# Board1.net
KiCad netlist of a schematic drawn in EasyEDA Pro
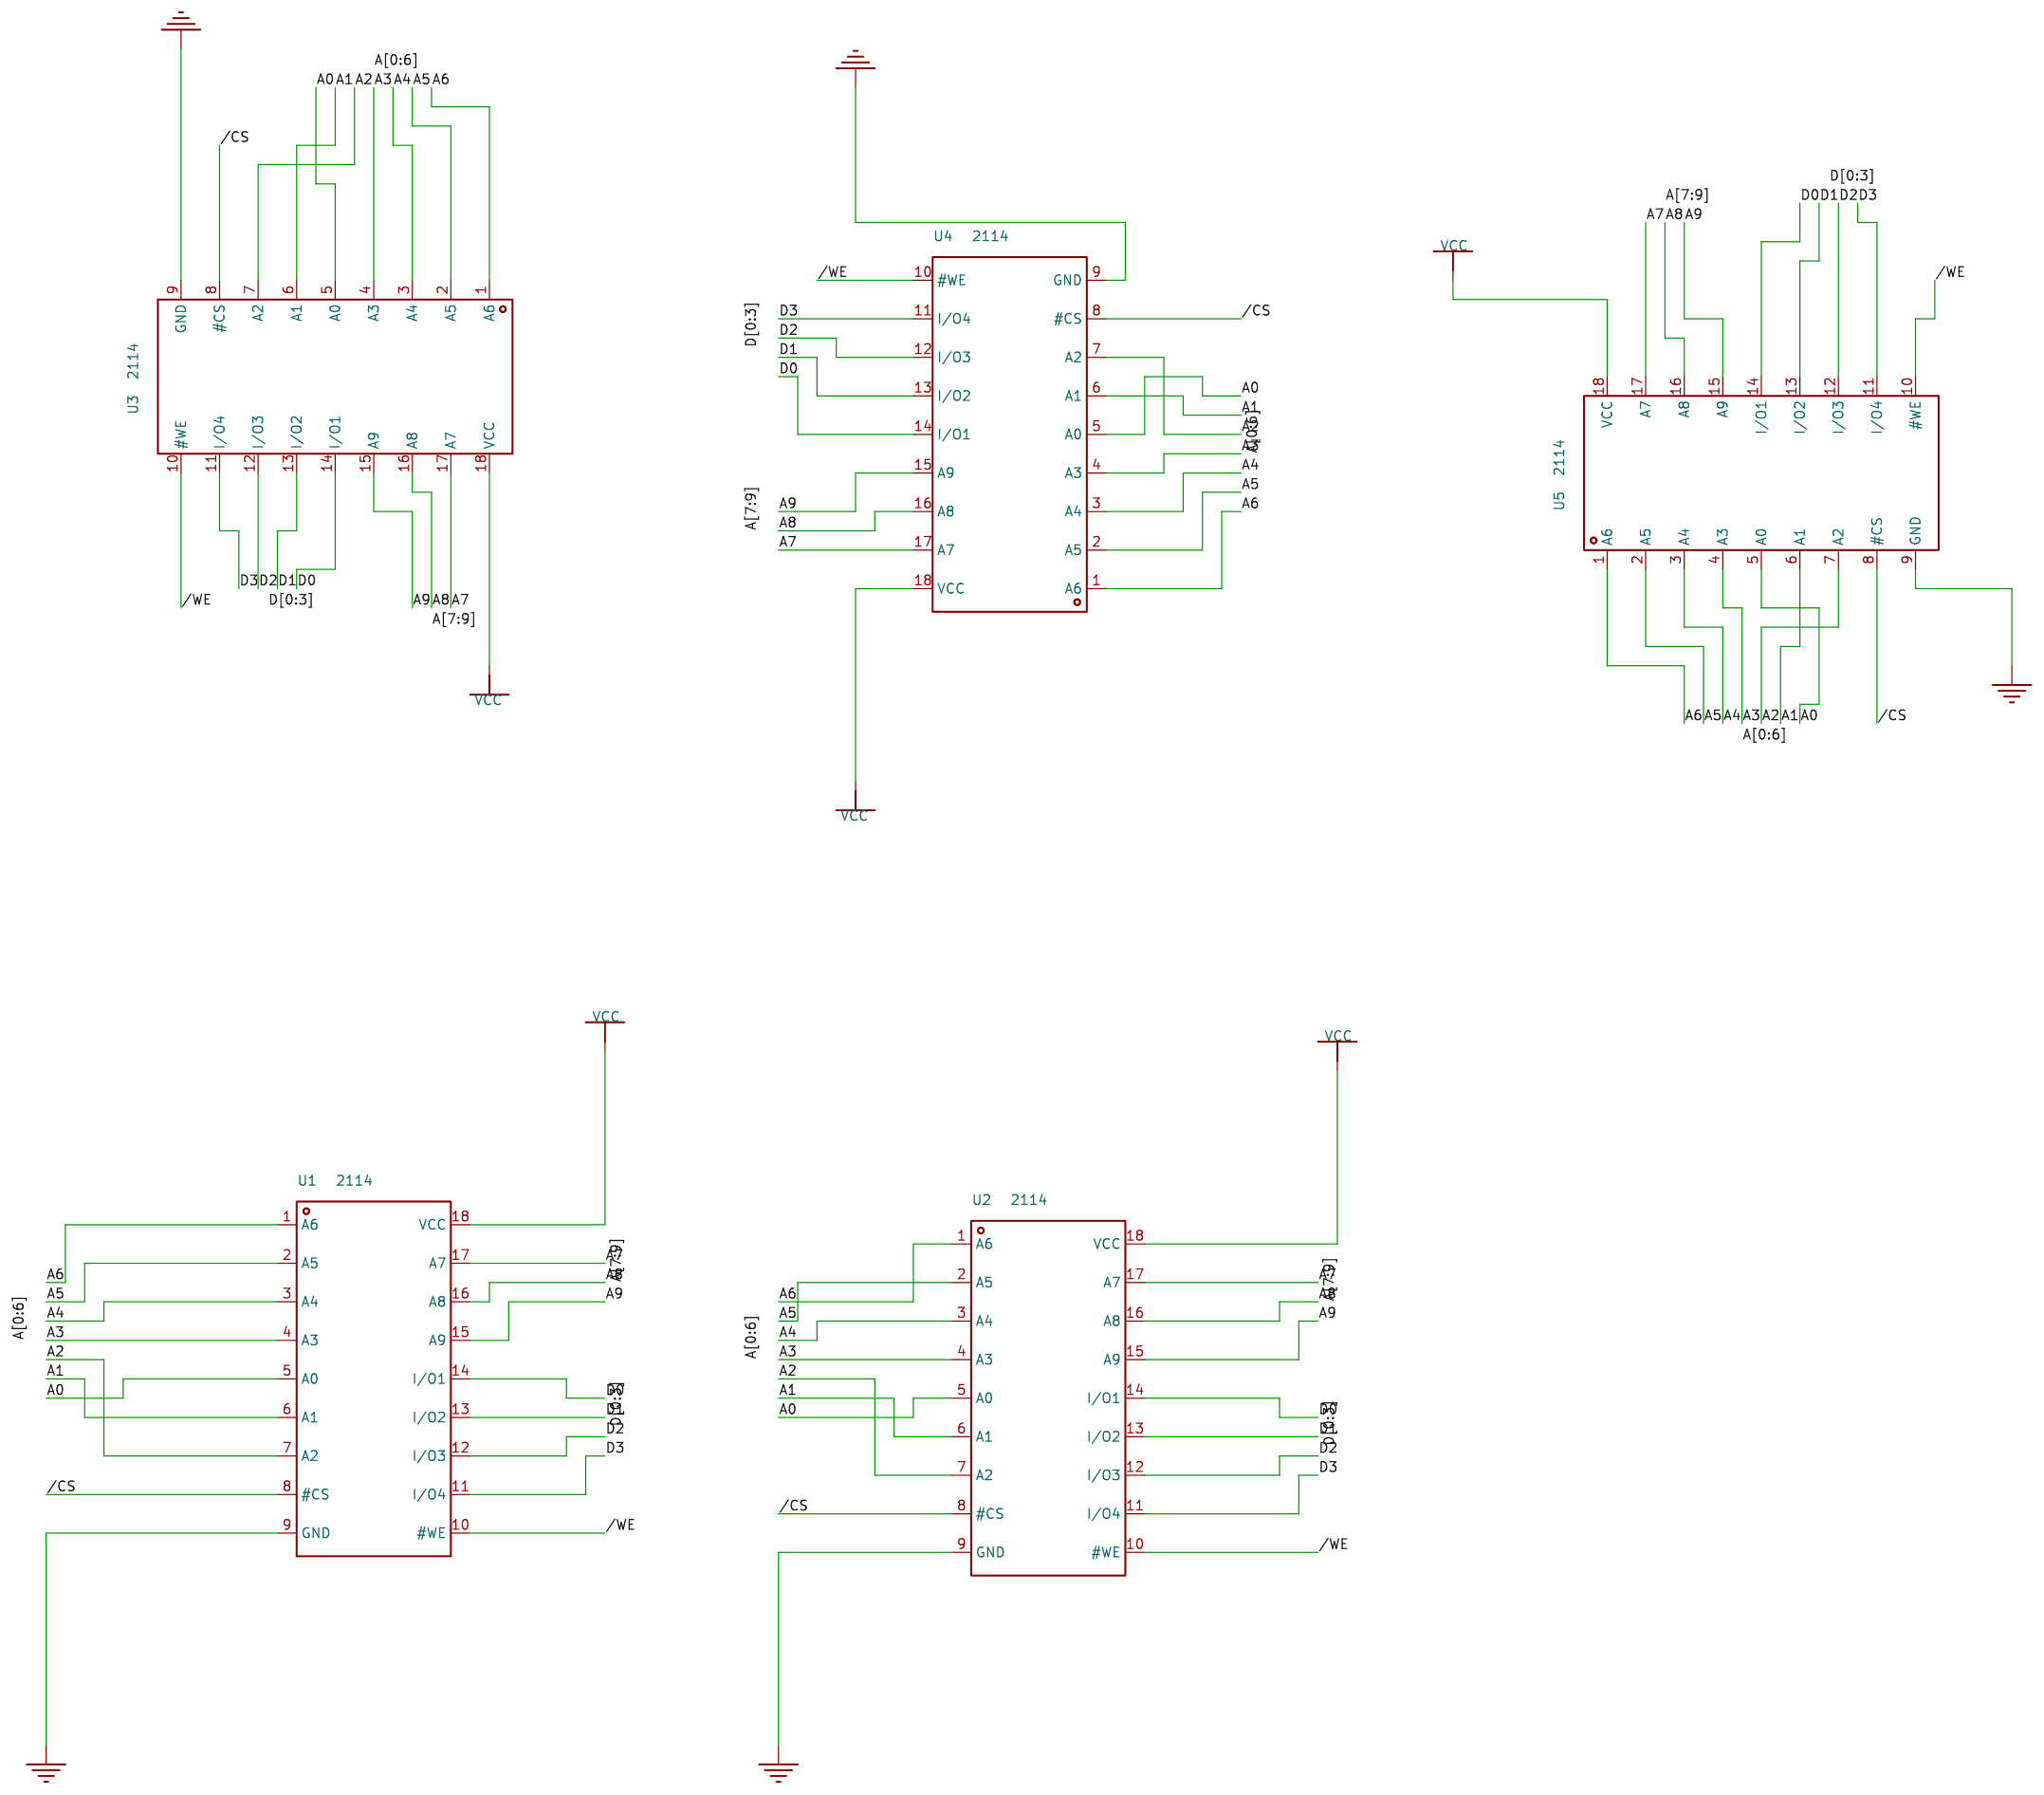
[diagram p0: schematic sheet]

(export (version "E")
  (design (tool "Eeschema 10.0.6"))
  (components
    (comp (ref "U1")
      (value "2114")
      (footprint "easyedapro:DIP-18_L23.0-W6.5-P2.54-LS7.6-BL")
      (fields (field (name "Manufacturer") "UTC"))
      (libsource (lib "easyedapro") (part "2114"))
    )
    (comp (ref "U2")
      (value "2114")
      (footprint "easyedapro:DIP-18_L23.0-W6.5-P2.54-LS7.6-BL")
      (fields (field (name "Manufacturer") "UTC"))
      (libsource (lib "easyedapro") (part "2114"))
    )
    (comp (ref "U3")
      (value "2114")
      (footprint "easyedapro:DIP-18_L23.0-W6.5-P2.54-LS7.6-BL")
      (fields (field (name "Manufacturer") "UTC"))
      (libsource (lib "easyedapro") (part "2114"))
    )
    (comp (ref "U4")
      (value "2114")
      (footprint "easyedapro:DIP-18_L23.0-W6.5-P2.54-LS7.6-BL")
      (fields (field (name "Manufacturer") "UTC"))
      (libsource (lib "easyedapro") (part "2114"))
    )
    (comp (ref "U5")
      (value "2114")
      (footprint "easyedapro:DIP-18_L23.0-W6.5-P2.54-LS7.6-BL")
      (fields (field (name "Manufacturer") "UTC"))
      (libsource (lib "easyedapro") (part "2114"))
    )
  )
  (nets
    (net (code "1") (name "/A0") (class "Default")
      (node (ref "U1") (pin "5") (pinfunction "A0_5") (pintype "unspecified"))
      (node (ref "U2") (pin "5") (pinfunction "A0_5") (pintype "unspecified"))
      (node (ref "U3") (pin "5") (pinfunction "A0_5") (pintype "unspecified"))
      (node (ref "U4") (pin "5") (pinfunction "A0_5") (pintype "unspecified"))
      (node (ref "U5") (pin "5") (pinfunction "A0_5") (pintype "unspecified"))
    )
    (net (code "2") (name "/A1") (class "Default")
      (node (ref "U1") (pin "6") (pinfunction "A1_6") (pintype "unspecified"))
      (node (ref "U2") (pin "6") (pinfunction "A1_6") (pintype "unspecified"))
      (node (ref "U3") (pin "6") (pinfunction "A1_6") (pintype "unspecified"))
      (node (ref "U4") (pin "6") (pinfunction "A1_6") (pintype "unspecified"))
      (node (ref "U5") (pin "6") (pinfunction "A1_6") (pintype "unspecified"))
    )
    (net (code "3") (name "/A2") (class "Default")
      (node (ref "U1") (pin "7") (pinfunction "A2_7") (pintype "unspecified"))
      (node (ref "U2") (pin "7") (pinfunction "A2_7") (pintype "unspecified"))
      (node (ref "U3") (pin "7") (pinfunction "A2_7") (pintype "unspecified"))
      (node (ref "U4") (pin "7") (pinfunction "A2_7") (pintype "unspecified"))
      (node (ref "U5") (pin "7") (pinfunction "A2_7") (pintype "unspecified"))
    )
    (net (code "4") (name "/A3") (class "Default")
      (node (ref "U1") (pin "4") (pinfunction "A3_4") (pintype "unspecified"))
      (node (ref "U2") (pin "4") (pinfunction "A3_4") (pintype "unspecified"))
      (node (ref "U3") (pin "4") (pinfunction "A3_4") (pintype "unspecified"))
      (node (ref "U4") (pin "4") (pinfunction "A3_4") (pintype "unspecified"))
      (node (ref "U5") (pin "4") (pinfunction "A3_4") (pintype "unspecified"))
    )
    (net (code "5") (name "/A4") (class "Default")
      (node (ref "U1") (pin "3") (pinfunction "A4_3") (pintype "unspecified"))
      (node (ref "U2") (pin "3") (pinfunction "A4_3") (pintype "unspecified"))
      (node (ref "U3") (pin "3") (pinfunction "A4_3") (pintype "unspecified"))
      (node (ref "U4") (pin "3") (pinfunction "A4_3") (pintype "unspecified"))
      (node (ref "U5") (pin "3") (pinfunction "A4_3") (pintype "unspecified"))
    )
    (net (code "6") (name "/A5") (class "Default")
      (node (ref "U1") (pin "2") (pinfunction "A5_2") (pintype "unspecified"))
      (node (ref "U2") (pin "2") (pinfunction "A5_2") (pintype "unspecified"))
      (node (ref "U3") (pin "2") (pinfunction "A5_2") (pintype "unspecified"))
      (node (ref "U4") (pin "2") (pinfunction "A5_2") (pintype "unspecified"))
      (node (ref "U5") (pin "2") (pinfunction "A5_2") (pintype "unspecified"))
    )
    (net (code "7") (name "/A6") (class "Default")
      (node (ref "U1") (pin "1") (pinfunction "A6_1") (pintype "unspecified"))
      (node (ref "U2") (pin "1") (pinfunction "A6_1") (pintype "unspecified"))
      (node (ref "U3") (pin "1") (pinfunction "A6_1") (pintype "unspecified"))
      (node (ref "U4") (pin "1") (pinfunction "A6_1") (pintype "unspecified"))
      (node (ref "U5") (pin "1") (pinfunction "A6_1") (pintype "unspecified"))
    )
    (net (code "8") (name "/A7") (class "Default")
      (node (ref "U1") (pin "17") (pinfunction "A7_17") (pintype "unspecified"))
      (node (ref "U2") (pin "17") (pinfunction "A7_17") (pintype "unspecified"))
      (node (ref "U3") (pin "17") (pinfunction "A7_17") (pintype "unspecified"))
      (node (ref "U4") (pin "17") (pinfunction "A7_17") (pintype "unspecified"))
      (node (ref "U5") (pin "17") (pinfunction "A7_17") (pintype "unspecified"))
    )
    (net (code "9") (name "/A8") (class "Default")
      (node (ref "U1") (pin "16") (pinfunction "A8_16") (pintype "unspecified"))
      (node (ref "U2") (pin "16") (pinfunction "A8_16") (pintype "unspecified"))
      (node (ref "U3") (pin "16") (pinfunction "A8_16") (pintype "unspecified"))
      (node (ref "U4") (pin "16") (pinfunction "A8_16") (pintype "unspecified"))
      (node (ref "U5") (pin "16") (pinfunction "A8_16") (pintype "unspecified"))
    )
    (net (code "10") (name "/A9") (class "Default")
      (node (ref "U1") (pin "15") (pinfunction "A9_15") (pintype "unspecified"))
      (node (ref "U2") (pin "15") (pinfunction "A9_15") (pintype "unspecified"))
      (node (ref "U3") (pin "15") (pinfunction "A9_15") (pintype "unspecified"))
      (node (ref "U4") (pin "15") (pinfunction "A9_15") (pintype "unspecified"))
      (node (ref "U5") (pin "15") (pinfunction "A9_15") (pintype "unspecified"))
    )
    (net (code "13") (name "/D0") (class "Default")
      (node (ref "U1") (pin "14") (pinfunction "I/O1_14") (pintype "unspecified"))
      (node (ref "U2") (pin "14") (pinfunction "I/O1_14") (pintype "unspecified"))
      (node (ref "U3") (pin "14") (pinfunction "I/O1_14") (pintype "unspecified"))
      (node (ref "U4") (pin "14") (pinfunction "I/O1_14") (pintype "unspecified"))
      (node (ref "U5") (pin "14") (pinfunction "I/O1_14") (pintype "unspecified"))
    )
    (net (code "14") (name "/D1") (class "Default")
      (node (ref "U1") (pin "13") (pinfunction "I/O2_13") (pintype "unspecified"))
      (node (ref "U2") (pin "13") (pinfunction "I/O2_13") (pintype "unspecified"))
      (node (ref "U3") (pin "13") (pinfunction "I/O2_13") (pintype "unspecified"))
      (node (ref "U4") (pin "13") (pinfunction "I/O2_13") (pintype "unspecified"))
      (node (ref "U5") (pin "13") (pinfunction "I/O2_13") (pintype "unspecified"))
    )
    (net (code "15") (name "/D2") (class "Default")
      (node (ref "U1") (pin "12") (pinfunction "I/O3_12") (pintype "unspecified"))
      (node (ref "U2") (pin "12") (pinfunction "I/O3_12") (pintype "unspecified"))
      (node (ref "U3") (pin "12") (pinfunction "I/O3_12") (pintype "unspecified"))
      (node (ref "U4") (pin "12") (pinfunction "I/O3_12") (pintype "unspecified"))
      (node (ref "U5") (pin "12") (pinfunction "I/O3_12") (pintype "unspecified"))
    )
    (net (code "16") (name "/D3") (class "Default")
      (node (ref "U1") (pin "11") (pinfunction "I/O4_11") (pintype "unspecified"))
      (node (ref "U2") (pin "11") (pinfunction "I/O4_11") (pintype "unspecified"))
      (node (ref "U3") (pin "11") (pinfunction "I/O4_11") (pintype "unspecified"))
      (node (ref "U4") (pin "11") (pinfunction "I/O4_11") (pintype "unspecified"))
      (node (ref "U5") (pin "11") (pinfunction "I/O4_11") (pintype "unspecified"))
    )
    (net (code "18") (name "/{slash}CS") (class "Default")
      (node (ref "U1") (pin "8") (pinfunction "#CS_8") (pintype "unspecified"))
      (node (ref "U2") (pin "8") (pinfunction "#CS_8") (pintype "unspecified"))
      (node (ref "U3") (pin "8") (pinfunction "#CS_8") (pintype "unspecified"))
      (node (ref "U4") (pin "8") (pinfunction "#CS_8") (pintype "unspecified"))
      (node (ref "U5") (pin "8") (pinfunction "#CS_8") (pintype "unspecified"))
    )
    (net (code "19") (name "/{slash}WE") (class "Default")
      (node (ref "U1") (pin "10") (pinfunction "#WE_10") (pintype "unspecified"))
      (node (ref "U2") (pin "10") (pinfunction "#WE_10") (pintype "unspecified"))
      (node (ref "U3") (pin "10") (pinfunction "#WE_10") (pintype "unspecified"))
      (node (ref "U4") (pin "10") (pinfunction "#WE_10") (pintype "unspecified"))
      (node (ref "U5") (pin "10") (pinfunction "#WE_10") (pintype "unspecified"))
    )
    (net (code "20") (name "GND") (class "Default")
      (node (ref "U1") (pin "9") (pinfunction "GND_9") (pintype "unspecified"))
      (node (ref "U2") (pin "9") (pinfunction "GND_9") (pintype "unspecified"))
      (node (ref "U3") (pin "9") (pinfunction "GND_9") (pintype "unspecified"))
      (node (ref "U4") (pin "9") (pinfunction "GND_9") (pintype "unspecified"))
      (node (ref "U5") (pin "9") (pinfunction "GND_9") (pintype "unspecified"))
    )
    (net (code "21") (name "VCC") (class "Default")
      (node (ref "U1") (pin "18") (pinfunction "VCC_18") (pintype "unspecified"))
      (node (ref "U2") (pin "18") (pinfunction "VCC_18") (pintype "unspecified"))
      (node (ref "U3") (pin "18") (pinfunction "VCC_18") (pintype "unspecified"))
      (node (ref "U4") (pin "18") (pinfunction "VCC_18") (pintype "unspecified"))
      (node (ref "U5") (pin "18") (pinfunction "VCC_18") (pintype "unspecified"))
    )
  )
)
